# Wireless_Temp_Sensor_Board_v1.net
KiCad netlist of a schematic drawn in EAGLE
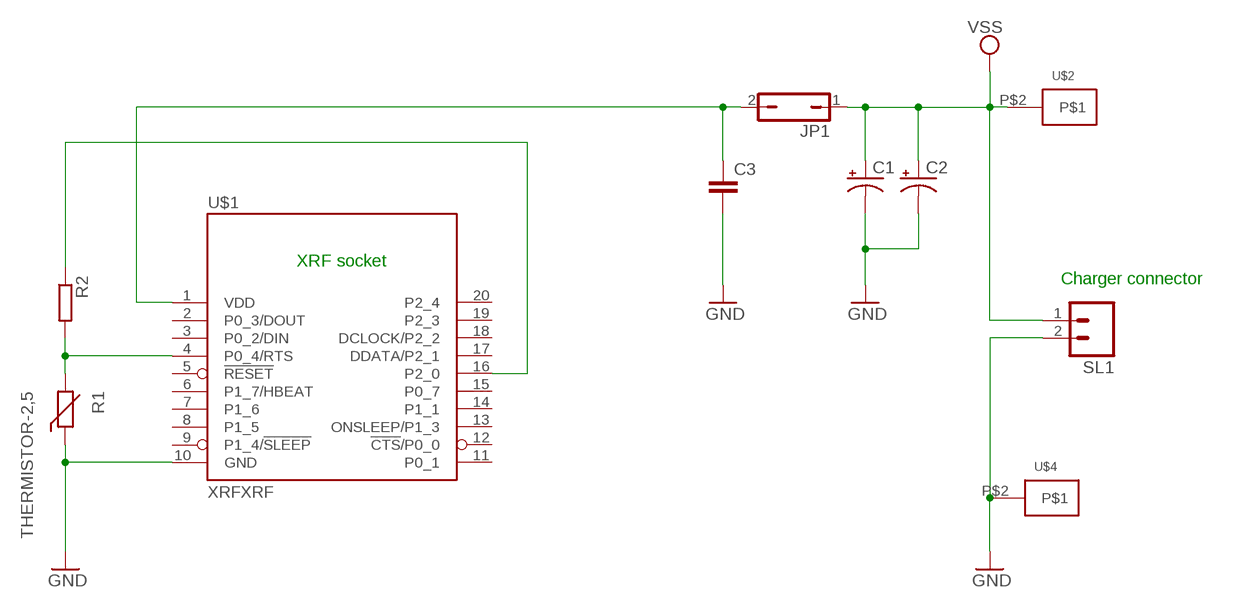
[diagram p0: schematic, sheet 1]

(export (version "E")
  (design (tool "Eeschema 10.0.6"))
  (components
    (comp (ref "C1")
      (value "CPOL-USE5-10.5")
      (footprint "eagle-import:E5-10,5")
      (libsource (lib "eagle-import") (part "CPOL-USE5-10.5"))
    )
    (comp (ref "C2")
      (value "CPOL-USE3.5-8")
      (footprint "eagle-import:E3,5-8")
      (libsource (lib "eagle-import") (part "CPOL-USE3.5-8"))
    )
    (comp (ref "C3")
      (value "C-EU025-025X050")
      (footprint "eagle-import:C025-025X050")
      (libsource (lib "eagle-import") (part "C-EU025-025X050"))
    )
    (comp (ref "JP1")
      (value "JP1Q")
      (footprint "eagle-import:JP1")
      (libsource (lib "eagle-import") (part "JP1Q"))
    )
    (comp (ref "R1")
      (value "THERMISTOR-2,5")
      (footprint "eagle-import:RS-2,5")
      (libsource (lib "eagle-import") (part "THERMISTOR-2,5"))
    )
    (comp (ref "R2")
      (value "R-EU_0207/12")
      (footprint "eagle-import:0207_12")
      (libsource (lib "eagle-import") (part "R-EU_0207/12"))
    )
    (comp (ref "SL1")
      (value "M02")
      (footprint "eagle-import:02P")
      (libsource (lib "eagle-import") (part "M02"))
    )
    (comp (ref "U$1")
      (value "XRFXRF")
      (footprint "eagle-import:XRF")
      (libsource (lib "eagle-import") (part "XRFXRF"))
    )
    (comp (ref "U$2")
      (value "HORSESHOEDPAD")
      (footprint "eagle-import:HORSESHOEPAD")
      (libsource (lib "eagle-import") (part "HORSESHOEDPAD"))
    )
    (comp (ref "U$4")
      (value "HORSESHOEDPAD")
      (footprint "eagle-import:HORSESHOEPAD")
      (libsource (lib "eagle-import") (part "HORSESHOEDPAD"))
    )
  )
  (nets
    (net (code "1") (name "GND") (class "Default")
      (node (ref "C1") (pin "-") (pinfunction "-_-") (pintype "passive"))
      (node (ref "C2") (pin "-") (pinfunction "-_-") (pintype "passive"))
      (node (ref "C3") (pin "2") (pinfunction "2_2") (pintype "passive"))
      (node (ref "R1") (pin "1") (pinfunction "1_1") (pintype "passive"))
      (node (ref "SL1") (pin "2") (pinfunction "2_2") (pintype "passive"))
      (node (ref "U$1") (pin "10") (pinfunction "GND_10") (pintype "power_in"))
      (node (ref "U$4") (pin "P$2") (pinfunction "P$1_P$2") (pintype "bidirectional"))
    )
    (net (code "2") (name "Net-(U$1-P0_4{slash}RTS)") (class "Default")
      (node (ref "R1") (pin "2") (pinfunction "2_2") (pintype "passive"))
      (node (ref "R2") (pin "2") (pinfunction "2_2") (pintype "passive"))
      (node (ref "U$1") (pin "4") (pinfunction "P0_4/RTS_4") (pintype "bidirectional"))
    )
    (net (code "3") (name "Net-(U$1-P2_0)") (class "Default")
      (node (ref "R2") (pin "1") (pinfunction "1_1") (pintype "passive"))
      (node (ref "U$1") (pin "16") (pinfunction "P2_0_16") (pintype "input"))
    )
    (net (code "4") (name "Net-(U$1-VDD)") (class "Default")
      (node (ref "C3") (pin "1") (pinfunction "1_1") (pintype "passive"))
      (node (ref "JP1") (pin "2") (pinfunction "2_2") (pintype "passive"))
      (node (ref "U$1") (pin "1") (pinfunction "VDD_1") (pintype "power_in"))
    )
    (net (code "5") (name "VSS") (class "Default")
      (node (ref "C1") (pin "+") (pinfunction "+_+") (pintype "passive"))
      (node (ref "C2") (pin "+") (pinfunction "+_+") (pintype "passive"))
      (node (ref "JP1") (pin "1") (pinfunction "1_1") (pintype "passive"))
      (node (ref "SL1") (pin "1") (pinfunction "1_1") (pintype "passive"))
      (node (ref "U$2") (pin "P$2") (pinfunction "P$1_P$2") (pintype "bidirectional"))
    )
    (net (code "6") (name "unconnected-(U$1-DCLOCK{slash}P2_2-Pad18)") (class "Default")
      (node (ref "U$1") (pin "18") (pinfunction "DCLOCK/P2_2_18") (pintype "bidirectional"))
    )
    (net (code "7") (name "unconnected-(U$1-DDATA{slash}P2_1-Pad17)") (class "Default")
      (node (ref "U$1") (pin "17") (pinfunction "DDATA/P2_1_17") (pintype "bidirectional"))
    )
    (net (code "8") (name "unconnected-(U$1-ONSLEEP{slash}P1_3-Pad13)") (class "Default")
      (node (ref "U$1") (pin "13") (pinfunction "ONSLEEP/P1_3_13") (pintype "bidirectional"))
    )
    (net (code "9") (name "unconnected-(U$1-P0_1-Pad11)") (class "Default")
      (node (ref "U$1") (pin "11") (pinfunction "P0_1_11") (pintype "bidirectional"))
    )
    (net (code "10") (name "unconnected-(U$1-P0_2{slash}DIN-Pad3)") (class "Default")
      (node (ref "U$1") (pin "3") (pinfunction "P0_2/DIN_3") (pintype "input"))
    )
    (net (code "11") (name "unconnected-(U$1-P0_3{slash}DOUT-Pad2)") (class "Default")
      (node (ref "U$1") (pin "2") (pinfunction "P0_3/DOUT_2") (pintype "output"))
    )
    (net (code "12") (name "unconnected-(U$1-P0_7-Pad15)") (class "Default")
      (node (ref "U$1") (pin "15") (pinfunction "P0_7_15") (pintype "bidirectional"))
    )
    (net (code "13") (name "unconnected-(U$1-P1_1-Pad14)") (class "Default")
      (node (ref "U$1") (pin "14") (pinfunction "P1_1_14") (pintype "bidirectional"))
    )
    (net (code "14") (name "unconnected-(U$1-P1_4{slash}~{SLEEP}-Pad9)") (class "Default")
      (node (ref "U$1") (pin "9") (pinfunction "P1_4/~{SLEEP}_9") (pintype "bidirectional"))
    )
    (net (code "15") (name "unconnected-(U$1-P1_5-Pad8)") (class "Default")
      (node (ref "U$1") (pin "8") (pinfunction "P1_5_8") (pintype "bidirectional"))
    )
    (net (code "16") (name "unconnected-(U$1-P1_6-Pad7)") (class "Default")
      (node (ref "U$1") (pin "7") (pinfunction "P1_6_7") (pintype "bidirectional"))
    )
    (net (code "17") (name "unconnected-(U$1-P1_7{slash}HBEAT-Pad6)") (class "Default")
      (node (ref "U$1") (pin "6") (pinfunction "P1_7/HBEAT_6") (pintype "bidirectional"))
    )
    (net (code "18") (name "unconnected-(U$1-P2_3-Pad19)") (class "Default")
      (node (ref "U$1") (pin "19") (pinfunction "P2_3_19") (pintype "bidirectional"))
    )
    (net (code "19") (name "unconnected-(U$1-P2_4-Pad20)") (class "Default")
      (node (ref "U$1") (pin "20") (pinfunction "P2_4_20") (pintype "bidirectional"))
    )
    (net (code "20") (name "unconnected-(U$1-~{CTS}{slash}P0_0-Pad12)") (class "Default")
      (node (ref "U$1") (pin "12") (pinfunction "~{CTS}/P0_0_12") (pintype "output"))
    )
    (net (code "21") (name "unconnected-(U$1-~{RESET}-Pad5)") (class "Default")
      (node (ref "U$1") (pin "5") (pinfunction "~{RESET}_5") (pintype "input"))
    )
  )
)
